# MyRollerShutter_nrf_1-3.net
KiCad netlist of a schematic drawn in EAGLE
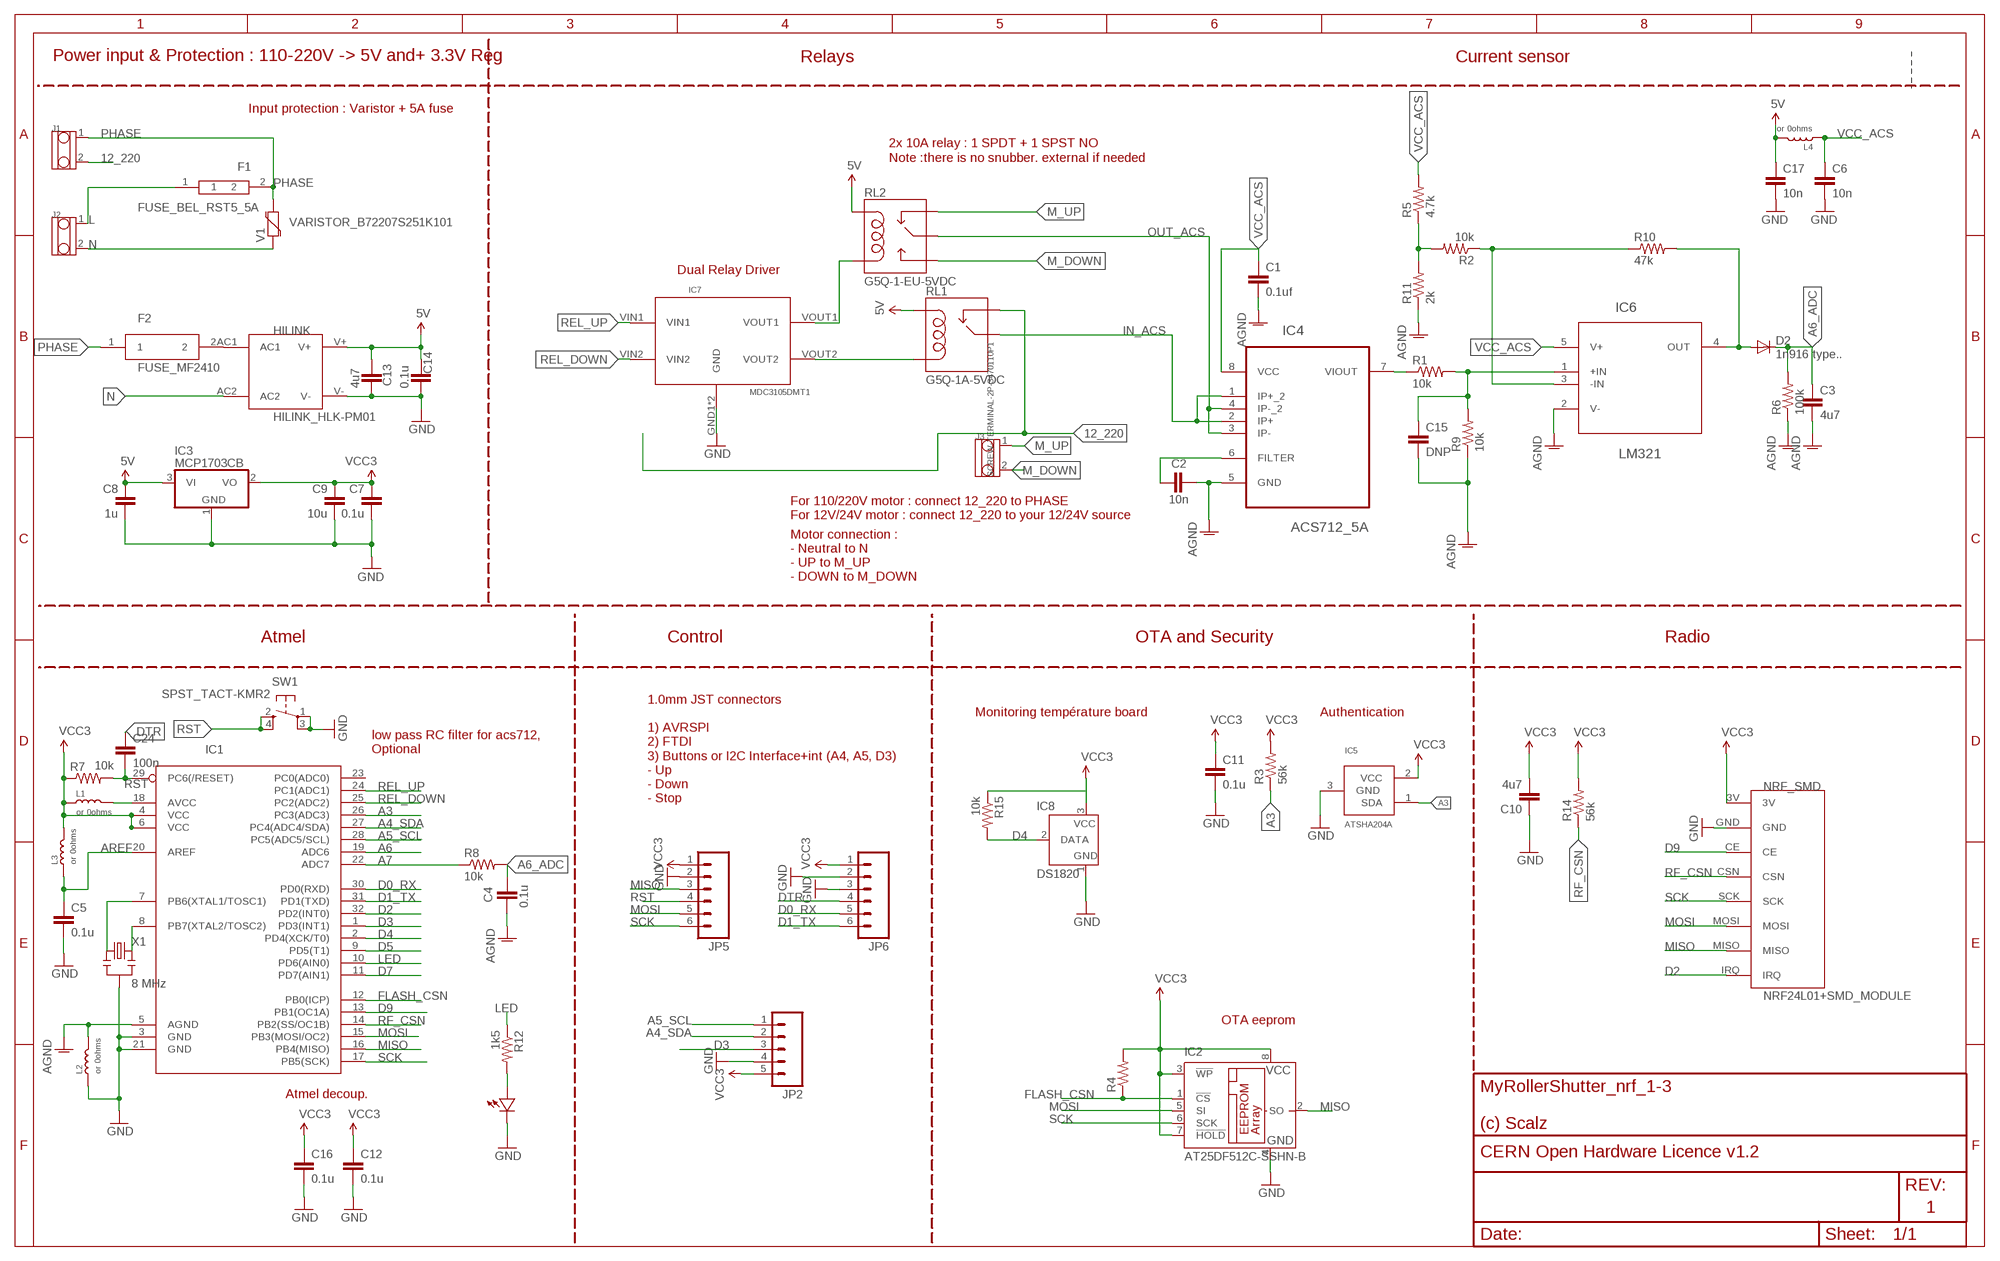
[diagram p0: schematic, sheet 1]

(export (version "E")
  (design (tool "Eeschema 10.0.6"))
  (components
    (comp (ref "C1")
      (value "0.1uf")
      (footprint "eagle-import:0805-CAP")
      (libsource (lib "eagle-import") (part "CAP0805-CAP"))
    )
    (comp (ref "C2")
      (value "10n")
      (footprint "eagle-import:0805-CAP")
      (libsource (lib "eagle-import") (part "CAP0805-CAP"))
    )
    (comp (ref "C3")
      (value "4u7")
      (footprint "eagle-import:0805-CAP")
      (libsource (lib "eagle-import") (part "CAP0805-CAP"))
    )
    (comp (ref "C4")
      (value "0.1u")
      (footprint "eagle-import:0805-CAP")
      (libsource (lib "eagle-import") (part "CAP0805-CAP"))
    )
    (comp (ref "C5")
      (value "0.1u")
      (footprint "eagle-import:0805-CAP")
      (libsource (lib "eagle-import") (part "CAP0805-CAP"))
    )
    (comp (ref "C6")
      (value "10n")
      (footprint "eagle-import:0805-CAP")
      (libsource (lib "eagle-import") (part "CAP0805-CAP"))
    )
    (comp (ref "C7")
      (value "0.1u")
      (footprint "eagle-import:0805-CAP")
      (libsource (lib "eagle-import") (part "CAP0805-CAP"))
    )
    (comp (ref "C8")
      (value "1u")
      (footprint "eagle-import:0805-CAP")
      (libsource (lib "eagle-import") (part "CAP0805-CAP"))
    )
    (comp (ref "C9")
      (value "10u")
      (footprint "eagle-import:0805-CAP")
      (libsource (lib "eagle-import") (part "CAP0805-CAP"))
    )
    (comp (ref "C10")
      (value "4u7")
      (footprint "eagle-import:0805-CAP")
      (libsource (lib "eagle-import") (part "CAP0805-CAP"))
    )
    (comp (ref "C11")
      (value "0.1u")
      (footprint "eagle-import:0805-CAP")
      (libsource (lib "eagle-import") (part "CAP0805-CAP"))
    )
    (comp (ref "C12")
      (value "0.1u")
      (footprint "eagle-import:0805-CAP")
      (libsource (lib "eagle-import") (part "CAP0805-CAP"))
    )
    (comp (ref "C13")
      (value "4u7")
      (footprint "eagle-import:0805-CAP")
      (libsource (lib "eagle-import") (part "CAP0805-CAP"))
    )
    (comp (ref "C14")
      (value "0.1u")
      (footprint "eagle-import:0805-CAP")
      (libsource (lib "eagle-import") (part "CAP0805-CAP"))
    )
    (comp (ref "C15")
      (value "DNP")
      (footprint "eagle-import:0805-CAP")
      (libsource (lib "eagle-import") (part "CAP0805-CAP"))
    )
    (comp (ref "C16")
      (value "0.1u")
      (footprint "eagle-import:0805-CAP")
      (libsource (lib "eagle-import") (part "CAP0805-CAP"))
    )
    (comp (ref "C17")
      (value "10n")
      (footprint "eagle-import:0805-CAP")
      (libsource (lib "eagle-import") (part "CAP0805-CAP"))
    )
    (comp (ref "C24")
      (value "100n")
      (footprint "eagle-import:0805-CAP")
      (libsource (lib "eagle-import") (part "CAP0805-CAP"))
    )
    (comp (ref "D1")
      (value "LED0805")
      (footprint "eagle-import:0805-LED")
      (libsource (lib "eagle-import") (part "LED0805"))
    )
    (comp (ref "D2")
      (value "1n916 type..")
      (footprint "eagle-import:SOD-323")
      (libsource (lib "eagle-import") (part "DIODESOD"))
    )
    (comp (ref "F1")
      (value "FUSE_BEL_RST5_5A")
      (footprint "eagle-import:FUSE_BEL_RST5_5A")
      (libsource (lib "eagle-import") (part "FUSE_BEL_RST5_5A"))
    )
    (comp (ref "F2")
      (value "FUSE_MF2410")
      (footprint "eagle-import:2410")
      (libsource (lib "eagle-import") (part "FUSE_MF2410"))
    )
    (comp (ref "HILINK")
      (value "HILINK_HLK-PM01")
      (footprint "eagle-import:HILINK_HLK-PM01")
      (libsource (lib "eagle-import") (part "HILINK_HLK-PM01"))
    )
    (comp (ref "IC1")
      (value "ATMega-328")
      (footprint "eagle-import:TQFP32-08")
      (libsource (lib "eagle-import") (part "ATMEGA168/328TQFP32"))
    )
    (comp (ref "IC2")
      (value "AT25DF512C-SSHN-B")
      (footprint "eagle-import:SO-08")
      (fields (field (name "MF") "MICROCHIP") (field (name "MPN") "25AA080/SN"))
      (libsource (lib "eagle-import") (part "25SNAA080"))
    )
    (comp (ref "IC3")
      (value "MCP1703CB")
      (footprint "eagle-import:SOT23")
      (libsource (lib "eagle-import") (part "MCP1703CB"))
    )
    (comp (ref "IC4")
      (value "ACS712_5A")
      (footprint "eagle-import:SOIC127P600X175-8N")
      (fields (field (name "MPN") "ACS712ELCTR-20A-T"))
      (libsource (lib "eagle-import") (part "ACS712ELCTR-20A-T"))
    )
    (comp (ref "IC5")
      (value "ATSHA204A")
      (footprint "eagle-import:SOT23")
      (libsource (lib "eagle-import") (part "ATSHA204A"))
    )
    (comp (ref "IC6")
      (value "LM321")
      (footprint "eagle-import:SOT95P285X120-5N")
      (fields (field (name "MPN") "LM321MF"))
      (libsource (lib "eagle-import") (part "LM321MF"))
    )
    (comp (ref "IC7")
      (value "MDC3105DMT1")
      (footprint "eagle-import:MDC3105DMT1")
      (libsource (lib "eagle-import") (part "MDC3105DMT1"))
    )
    (comp (ref "IC8")
      (value "DS1820")
      (footprint "eagle-import:TO92-")
      (libsource (lib "eagle-import") (part "DS1820"))
    )
    (comp (ref "J1")
      (value "SCREW-TERMINAL-2P-3470110P1")
      (footprint "eagle-import:2P-5.0")
      (libsource (lib "eagle-import") (part "SCREW-TERMINAL-2P-3470110P1"))
    )
    (comp (ref "J2")
      (value "SCREW-TERMINAL-2P-3470110P1")
      (footprint "eagle-import:2P-5.0")
      (libsource (lib "eagle-import") (part "SCREW-TERMINAL-2P-3470110P1"))
    )
    (comp (ref "J3")
      (value "SCREW-TERMINAL-2P-3470110P1")
      (footprint "eagle-import:2P-5.0")
      (libsource (lib "eagle-import") (part "SCREW-TERMINAL-2P-3470110P1"))
    )
    (comp (ref "JP2")
      (value "M05SMD")
      (footprint "eagle-import:1X05-1MM")
      (libsource (lib "eagle-import") (part "M05SMD"))
    )
    (comp (ref "JP5")
      (value "M06SMD-1MM")
      (footprint "eagle-import:1X06-1MM")
      (libsource (lib "eagle-import") (part "M06SMD-1MM"))
    )
    (comp (ref "JP6")
      (value "M06SMD-1MM")
      (footprint "eagle-import:1X06-1MM")
      (libsource (lib "eagle-import") (part "M06SMD-1MM"))
    )
    (comp (ref "L1")
      (value "or 0ohms")
      (footprint "eagle-import:L0805")
      (libsource (lib "eagle-import") (part "INDUCTOR/FERRITE-BEAD-0805"))
    )
    (comp (ref "L2")
      (value "or 0ohms")
      (footprint "eagle-import:L0805")
      (libsource (lib "eagle-import") (part "INDUCTOR/FERRITE-BEAD-0805"))
    )
    (comp (ref "L3")
      (value "or 0ohms")
      (footprint "eagle-import:L0805")
      (libsource (lib "eagle-import") (part "INDUCTOR/FERRITE-BEAD-0805"))
    )
    (comp (ref "L4")
      (value "or 0ohms")
      (footprint "eagle-import:L0805")
      (libsource (lib "eagle-import") (part "INDUCTOR/FERRITE-BEAD-0805"))
    )
    (comp (ref "NRF_SMD")
      (value "NRF24L01+SMD_MODULE")
      (footprint "eagle-import:NRF24L01+SMD_MODULE")
      (libsource (lib "eagle-import") (part "NRF24L01+SMD_MODULE"))
    )
    (comp (ref "R1")
      (value "10k")
      (footprint "eagle-import:0805-RES")
      (libsource (lib "eagle-import") (part "RESISTOR0805-RES"))
    )
    (comp (ref "R2")
      (value "10k")
      (footprint "eagle-import:0805-RES")
      (libsource (lib "eagle-import") (part "RESISTOR0805-RES"))
    )
    (comp (ref "R3")
      (value "56k")
      (footprint "eagle-import:0805-RES")
      (libsource (lib "eagle-import") (part "RESISTOR0805-RES"))
    )
    (comp (ref "R4")
      (value "RESISTOR0805-RES")
      (footprint "eagle-import:0805-RES")
      (libsource (lib "eagle-import") (part "RESISTOR0805-RES"))
    )
    (comp (ref "R5")
      (value "4.7k")
      (footprint "eagle-import:0805-RES")
      (libsource (lib "eagle-import") (part "RESISTOR0805-RES"))
    )
    (comp (ref "R6")
      (value "100k")
      (footprint "eagle-import:0805-RES")
      (libsource (lib "eagle-import") (part "RESISTOR0805-RES"))
    )
    (comp (ref "R7")
      (value "10k")
      (footprint "eagle-import:0805-RES")
      (libsource (lib "eagle-import") (part "RESISTOR0805-RES"))
    )
    (comp (ref "R8")
      (value "10k")
      (footprint "eagle-import:0805-RES")
      (libsource (lib "eagle-import") (part "RESISTOR0805-RES"))
    )
    (comp (ref "R9")
      (value "10k")
      (footprint "eagle-import:0805-RES")
      (libsource (lib "eagle-import") (part "RESISTOR0805-RES"))
    )
    (comp (ref "R10")
      (value "47k")
      (footprint "eagle-import:0805-RES")
      (libsource (lib "eagle-import") (part "RESISTOR0805-RES"))
    )
    (comp (ref "R11")
      (value "2k")
      (footprint "eagle-import:0805-RES")
      (libsource (lib "eagle-import") (part "RESISTOR0805-RES"))
    )
    (comp (ref "R12")
      (value "1k5")
      (footprint "eagle-import:0805-RES")
      (libsource (lib "eagle-import") (part "RESISTOR0805-RES"))
    )
    (comp (ref "R14")
      (value "56k")
      (footprint "eagle-import:0805-RES")
      (libsource (lib "eagle-import") (part "RESISTOR0805-RES"))
    )
    (comp (ref "R15")
      (value "10k")
      (footprint "eagle-import:0805-RES")
      (libsource (lib "eagle-import") (part "RESISTOR0805-RES"))
    )
    (comp (ref "RL1")
      (value "G5Q-1A-5VDC")
      (footprint "eagle-import:G5Q_SINGLE")
      (libsource (lib "eagle-import") (part "G5Q_SINGLE"))
    )
    (comp (ref "RL2")
      (value "G5Q-1-EU-5VDC")
      (footprint "eagle-import:RELAY-G5Q")
      (libsource (lib "eagle-import") (part "RELAYPTH"))
    )
    (comp (ref "SW1")
      (value "SPST_TACT-KMR2")
      (footprint "eagle-import:KMR2")
      (libsource (lib "eagle-import") (part "SPST_TACT-KMR2"))
    )
    (comp (ref "V1")
      (value "VARISTOR_B72207S251K101")
      (footprint "eagle-import:VARISTOR_B72207S251K101")
      (libsource (lib "eagle-import") (part "VARISTOR_B72207S251K101"))
    )
    (comp (ref "X1")
      (value "8 MHz")
      (footprint "eagle-import:RESONATOR-SMD")
      (libsource (lib "eagle-import") (part "RESONATORSMD"))
    )
  )
  (nets
    (net (code "1") (name "/A4_SDA") (class "Default")
      (node (ref "IC1") (pin "27") (pinfunction "PC4(ADC4/SDA)_27") (pintype "bidirectional"))
      (node (ref "JP2") (pin "2") (pinfunction "2_2") (pintype "passive"))
    )
    (net (code "2") (name "/A5_SCL") (class "Default")
      (node (ref "IC1") (pin "28") (pinfunction "PC5(ADC5/SCL)_28") (pintype "bidirectional"))
      (node (ref "JP2") (pin "1") (pinfunction "1_1") (pintype "passive"))
    )
    (net (code "3") (name "/A6") (class "Default")
      (node (ref "IC1") (pin "19") (pinfunction "ADC6_19") (pintype "bidirectional"))
    )
    (net (code "4") (name "/A7") (class "Default")
      (node (ref "IC1") (pin "22") (pinfunction "ADC7_22") (pintype "bidirectional"))
      (node (ref "R8") (pin "1") (pinfunction "1_1") (pintype "passive"))
    )
    (net (code "5") (name "/AREF") (class "Default")
      (node (ref "C5") (pin "1") (pinfunction "1_1") (pintype "passive"))
      (node (ref "IC1") (pin "20") (pinfunction "AREF_20") (pintype "bidirectional"))
      (node (ref "L3") (pin "1") (pinfunction "1_1") (pintype "passive"))
    )
    (net (code "6") (name "/D0_RX") (class "Default")
      (node (ref "IC1") (pin "30") (pinfunction "PD0(RXD)_30") (pintype "bidirectional"))
      (node (ref "JP6") (pin "5") (pinfunction "5_5") (pintype "passive"))
    )
    (net (code "7") (name "/D1_TX") (class "Default")
      (node (ref "IC1") (pin "31") (pinfunction "PD1(TXD)_31") (pintype "bidirectional"))
      (node (ref "JP6") (pin "6") (pinfunction "6_6") (pintype "passive"))
    )
    (net (code "8") (name "/D2") (class "Default")
      (node (ref "IC1") (pin "32") (pinfunction "PD2(INT0)_32") (pintype "bidirectional"))
      (node (ref "NRF_SMD") (pin "IRQ") (pinfunction "IRQ_IRQ") (pintype "bidirectional"))
    )
    (net (code "9") (name "/D3") (class "Default")
      (node (ref "IC1") (pin "1") (pinfunction "PD3(INT1)_1") (pintype "bidirectional"))
      (node (ref "JP2") (pin "3") (pinfunction "3_3") (pintype "passive"))
    )
    (net (code "10") (name "/D4") (class "Default")
      (node (ref "IC1") (pin "2") (pinfunction "PD4(XCK/T0)_2") (pintype "bidirectional"))
      (node (ref "IC8") (pin "2") (pinfunction "DATA_2") (pintype "input"))
      (node (ref "R15") (pin "2") (pinfunction "2_2") (pintype "passive"))
    )
    (net (code "11") (name "/D5") (class "Default")
      (node (ref "IC1") (pin "9") (pinfunction "PD5(T1)_9") (pintype "bidirectional"))
    )
    (net (code "12") (name "/D7") (class "Default")
      (node (ref "IC1") (pin "11") (pinfunction "PD7(AIN1)_11") (pintype "bidirectional"))
    )
    (net (code "13") (name "/D9") (class "Default")
      (node (ref "IC1") (pin "13") (pinfunction "PB1(OC1A)_13") (pintype "bidirectional"))
      (node (ref "NRF_SMD") (pin "CE") (pinfunction "CE_CE") (pintype "bidirectional"))
    )
    (net (code "14") (name "/FLASH_CSN") (class "Default")
      (node (ref "IC1") (pin "12") (pinfunction "PB0(ICP)_12") (pintype "bidirectional"))
      (node (ref "IC2") (pin "1") (pinfunction "~{CS}_1") (pintype "input"))
      (node (ref "R4") (pin "1") (pinfunction "1_1") (pintype "passive"))
    )
    (net (code "15") (name "/IN_ACS") (class "Default")
      (node (ref "IC4") (pin "1") (pinfunction "IP+_2_1") (pintype "input"))
      (node (ref "IC4") (pin "2") (pinfunction "IP+_2") (pintype "input"))
      (node (ref "RL1") (pin "2") (pinfunction "MAIN_2") (pintype "bidirectional"))
    )
    (net (code "16") (name "/L") (class "Default")
      (node (ref "F1") (pin "1") (pinfunction "1_1") (pintype "bidirectional"))
      (node (ref "J2") (pin "1") (pinfunction "1_1") (pintype "bidirectional"))
    )
    (net (code "17") (name "/LED") (class "Default")
      (node (ref "IC1") (pin "10") (pinfunction "PD6(AIN0)_10") (pintype "bidirectional"))
      (node (ref "R12") (pin "1") (pinfunction "1_1") (pintype "passive"))
    )
    (net (code "18") (name "/MISO") (class "Default")
      (node (ref "IC1") (pin "16") (pinfunction "PB4(MISO)_16") (pintype "bidirectional"))
      (node (ref "IC2") (pin "2") (pinfunction "SO_2") (pintype "bidirectional"))
      (node (ref "JP5") (pin "3") (pinfunction "3_3") (pintype "passive"))
      (node (ref "NRF_SMD") (pin "MISO") (pinfunction "MISO_MISO") (pintype "bidirectional"))
    )
    (net (code "19") (name "/MOSI") (class "Default")
      (node (ref "IC1") (pin "15") (pinfunction "PB3(MOSI/OC2)_15") (pintype "bidirectional"))
      (node (ref "IC2") (pin "5") (pinfunction "SI_5") (pintype "input"))
      (node (ref "JP5") (pin "5") (pinfunction "5_5") (pintype "passive"))
      (node (ref "NRF_SMD") (pin "MOSI") (pinfunction "MOSI_MOSI") (pintype "bidirectional"))
    )
    (net (code "20") (name "/OUT_ACS") (class "Default")
      (node (ref "IC4") (pin "3") (pinfunction "IP-_3") (pintype "input"))
      (node (ref "IC4") (pin "4") (pinfunction "IP-_2_4") (pintype "input"))
      (node (ref "RL2") (pin "2") (pinfunction "MAIN_2") (pintype "bidirectional"))
    )
    (net (code "21") (name "/SCK") (class "Default")
      (node (ref "IC1") (pin "17") (pinfunction "PB5(SCK)_17") (pintype "bidirectional"))
      (node (ref "IC2") (pin "6") (pinfunction "SCK_6") (pintype "input"))
      (node (ref "JP5") (pin "6") (pinfunction "6_6") (pintype "passive"))
      (node (ref "NRF_SMD") (pin "SCK") (pinfunction "SCK_SCK") (pintype "bidirectional"))
    )
    (net (code "22") (name "5V") (class "Default")
      (node (ref "C13") (pin "1") (pinfunction "1_1") (pintype "passive"))
      (node (ref "C14") (pin "1") (pinfunction "1_1") (pintype "passive"))
      (node (ref "C17") (pin "1") (pinfunction "1_1") (pintype "passive"))
      (node (ref "C8") (pin "1") (pinfunction "1_1") (pintype "passive"))
      (node (ref "HILINK") (pin "V+") (pinfunction "V+_V+") (pintype "bidirectional"))
      (node (ref "IC3") (pin "3") (pinfunction "VI_3") (pintype "input"))
      (node (ref "L4") (pin "2") (pinfunction "2_2") (pintype "passive"))
      (node (ref "RL1") (pin "1") (pinfunction "COIL1_1") (pintype "bidirectional"))
      (node (ref "RL2") (pin "5") (pinfunction "COIL1_5") (pintype "bidirectional"))
    )
    (net (code "23") (name "12_220") (class "Default")
      (node (ref "J1") (pin "2") (pinfunction "2_2") (pintype "bidirectional"))
      (node (ref "RL1") (pin "3") (pinfunction "NC_3") (pintype "bidirectional"))
    )
    (net (code "24") (name "A3") (class "Default")
      (node (ref "IC1") (pin "26") (pinfunction "PC3(ADC3)_26") (pintype "bidirectional"))
      (node (ref "IC5") (pin "1") (pinfunction "SDA_1") (pintype "bidirectional"))
      (node (ref "R3") (pin "1") (pinfunction "1_1") (pintype "passive"))
    )
    (net (code "25") (name "A6_ADC") (class "Default")
      (node (ref "C3") (pin "1") (pinfunction "1_1") (pintype "passive"))
      (node (ref "C4") (pin "2") (pinfunction "2_2") (pintype "passive"))
      (node (ref "D2") (pin "1") (pinfunction "C_1") (pintype "passive"))
      (node (ref "R6") (pin "2") (pinfunction "2_2") (pintype "passive"))
      (node (ref "R8") (pin "2") (pinfunction "2_2") (pintype "passive"))
    )
    (net (code "26") (name "AGND") (class "Default")
      (node (ref "C1") (pin "2") (pinfunction "2_2") (pintype "passive"))
      (node (ref "C15") (pin "2") (pinfunction "2_2") (pintype "passive"))
      (node (ref "C2") (pin "2") (pinfunction "2_2") (pintype "passive"))
      (node (ref "C3") (pin "2") (pinfunction "2_2") (pintype "passive"))
      (node (ref "C4") (pin "1") (pinfunction "1_1") (pintype "passive"))
      (node (ref "IC1") (pin "5") (pinfunction "AGND_5") (pintype "bidirectional"))
      (node (ref "IC4") (pin "5") (pinfunction "GND_5") (pintype "passive"))
      (node (ref "IC6") (pin "2") (pinfunction "V-_2") (pintype "power_in"))
      (node (ref "L2") (pin "2") (pinfunction "2_2") (pintype "passive"))
      (node (ref "R11") (pin "1") (pinfunction "1_1") (pintype "passive"))
      (node (ref "R6") (pin "1") (pinfunction "1_1") (pintype "passive"))
      (node (ref "R9") (pin "1") (pinfunction "1_1") (pintype "passive"))
    )
    (net (code "27") (name "DTR") (class "Default")
      (node (ref "C24") (pin "1") (pinfunction "1_1") (pintype "passive"))
      (node (ref "JP6") (pin "4") (pinfunction "4_4") (pintype "passive"))
    )
    (net (code "28") (name "GND") (class "Default")
      (node (ref "C10") (pin "1") (pinfunction "1_1") (pintype "passive"))
      (node (ref "C11") (pin "2") (pinfunction "2_2") (pintype "passive"))
      (node (ref "C12") (pin "2") (pinfunction "2_2") (pintype "passive"))
      (node (ref "C13") (pin "2") (pinfunction "2_2") (pintype "passive"))
      (node (ref "C14") (pin "2") (pinfunction "2_2") (pintype "passive"))
      (node (ref "C16") (pin "2") (pinfunction "2_2") (pintype "passive"))
      (node (ref "C17") (pin "2") (pinfunction "2_2") (pintype "passive"))
      (node (ref "C5") (pin "2") (pinfunction "2_2") (pintype "passive"))
      (node (ref "C6") (pin "2") (pinfunction "2_2") (pintype "passive"))
      (node (ref "C7") (pin "2") (pinfunction "2_2") (pintype "passive"))
      (node (ref "C8") (pin "2") (pinfunction "2_2") (pintype "passive"))
      (node (ref "C9") (pin "2") (pinfunction "2_2") (pintype "passive"))
      (node (ref "D1") (pin "MINUS") (pinfunction "MINUS_MINUS") (pintype "passive"))
      (node (ref "HILINK") (pin "V-") (pinfunction "V-_V-") (pintype "bidirectional"))
      (node (ref "IC1") (pin "21") (pinfunction "GND_21") (pintype "bidirectional"))
      (node (ref "IC1") (pin "3") (pinfunction "GND_3") (pintype "bidirectional"))
      (node (ref "IC2") (pin "4") (pinfunction "GND_4") (pintype "power_in"))
      (node (ref "IC3") (pin "1") (pinfunction "GND_1") (pintype "passive"))
      (node (ref "IC5") (pin "3") (pinfunction "GND_3") (pintype "bidirectional"))
      (node (ref "IC7") (pin "GND1") (pinfunction "GND_GND1") (pintype "bidirectional"))
      (node (ref "IC7") (pin "GND2") (pinfunction "GND_GND2") (pintype "bidirectional"))
      (node (ref "IC8") (pin "1") (pinfunction "GND_1") (pintype "passive"))
      (node (ref "JP2") (pin "4") (pinfunction "4_4") (pintype "passive"))
      (node (ref "JP5") (pin "2") (pinfunction "2_2") (pintype "passive"))
      (node (ref "JP6") (pin "2") (pinfunction "2_2") (pintype "passive"))
      (node (ref "JP6") (pin "3") (pinfunction "3_3") (pintype "passive"))
      (node (ref "L2") (pin "1") (pinfunction "1_1") (pintype "passive"))
      (node (ref "NRF_SMD") (pin "GND") (pinfunction "GND_GND") (pintype "bidirectional"))
      (node (ref "SW1") (pin "1") (pinfunction "P_1") (pintype "passive"))
      (node (ref "SW1") (pin "3") (pinfunction "P1_3") (pintype "passive"))
      (node (ref "X1") (pin "2") (pinfunction "2_2") (pintype "passive"))
    )
    (net (code "29") (name "M_DOWN") (class "Default")
      (node (ref "J3") (pin "2") (pinfunction "2_2") (pintype "bidirectional"))
      (node (ref "RL2") (pin "3") (pinfunction "NO_3") (pintype "bidirectional"))
    )
    (net (code "30") (name "M_UP") (class "Default")
      (node (ref "J3") (pin "1") (pinfunction "1_1") (pintype "bidirectional"))
      (node (ref "RL2") (pin "4") (pinfunction "NC_4") (pintype "bidirectional"))
    )
    (net (code "31") (name "N") (class "Default")
      (node (ref "HILINK") (pin "AC2") (pinfunction "AC2_AC2") (pintype "bidirectional"))
      (node (ref "J2") (pin "2") (pinfunction "2_2") (pintype "bidirectional"))
      (node (ref "V1") (pin "1") (pinfunction "1_1") (pintype "passive"))
    )
    (net (code "32") (name "Net-(D1-PadPLUS)") (class "Default")
      (node (ref "D1") (pin "PLUS") (pinfunction "PLUS_PLUS") (pintype "passive"))
      (node (ref "R12") (pin "2") (pinfunction "2_2") (pintype "passive"))
    )
    (net (code "33") (name "Net-(D2-A)") (class "Default")
      (node (ref "D2") (pin "2") (pinfunction "A_2") (pintype "passive"))
      (node (ref "IC6") (pin "4") (pinfunction "OUT_4") (pintype "output"))
      (node (ref "R10") (pin "2") (pinfunction "2_2") (pintype "passive"))
    )
    (net (code "34") (name "Net-(F2-Pad2)") (class "Default")
      (node (ref "F2") (pin "2") (pinfunction "2_2") (pintype "bidirectional"))
      (node (ref "HILINK") (pin "AC1") (pinfunction "AC1_AC1") (pintype "bidirectional"))
    )
    (net (code "35") (name "Net-(IC1-AVCC)") (class "Default")
      (node (ref "IC1") (pin "18") (pinfunction "AVCC_18") (pintype "bidirectional"))
      (node (ref "L1") (pin "2") (pinfunction "2_2") (pintype "passive"))
    )
    (net (code "36") (name "Net-(IC1-PB6(XTAL1{slash}TOSC1))") (class "Default")
      (node (ref "IC1") (pin "7") (pinfunction "PB6(XTAL1/TOSC1)_7") (pintype "bidirectional"))
      (node (ref "X1") (pin "1") (pinfunction "1_1") (pintype "passive"))
    )
    (net (code "37") (name "Net-(IC1-PB7(XTAL2{slash}TOSC2))") (class "Default")
      (node (ref "IC1") (pin "8") (pinfunction "PB7(XTAL2/TOSC2)_8") (pintype "bidirectional"))
      (node (ref "X1") (pin "3") (pinfunction "3_3") (pintype "passive"))
    )
    (net (code "38") (name "Net-(IC4-FILTER)") (class "Default")
      (node (ref "C2") (pin "1") (pinfunction "1_1") (pintype "passive"))
      (node (ref "IC4") (pin "6") (pinfunction "FILTER_6") (pintype "input"))
    )
    (net (code "39") (name "Net-(IC4-VIOUT)") (class "Default")
      (node (ref "IC4") (pin "7") (pinfunction "VIOUT_7") (pintype "output"))
      (node (ref "R1") (pin "1") (pinfunction "1_1") (pintype "passive"))
    )
    (net (code "40") (name "Net-(IC6-+IN)") (class "Default")
      (node (ref "C15") (pin "1") (pinfunction "1_1") (pintype "passive"))
      (node (ref "IC6") (pin "1") (pinfunction "+IN_1") (pintype "input"))
      (node (ref "R1") (pin "2") (pinfunction "2_2") (pintype "passive"))
      (node (ref "R9") (pin "2") (pinfunction "2_2") (pintype "passive"))
    )
    (net (code "41") (name "Net-(IC6--IN)") (class "Default")
      (node (ref "IC6") (pin "3") (pinfunction "-IN_3") (pintype "input"))
      (node (ref "R10") (pin "1") (pinfunction "1_1") (pintype "passive"))
      (node (ref "R2") (pin "1") (pinfunction "1_1") (pintype "passive"))
    )
    (net (code "42") (name "Net-(R11-Pad2)") (class "Default")
      (node (ref "R11") (pin "2") (pinfunction "2_2") (pintype "passive"))
      (node (ref "R2") (pin "2") (pinfunction "2_2") (pintype "passive"))
      (node (ref "R5") (pin "1") (pinfunction "1_1") (pintype "passive"))
    )
    (net (code "43") (name "Net-(RL1-COIL2)") (class "Default")
      (node (ref "IC7") (pin "VOUT2") (pinfunction "VOUT2_VOUT2") (pintype "bidirectional"))
      (node (ref "RL1") (pin "5") (pinfunction "COIL2_5") (pintype "bidirectional"))
    )
    (net (code "44") (name "Net-(RL2-COIL2)") (class "Default")
      (node (ref "IC7") (pin "VOUT1") (pinfunction "VOUT1_VOUT1") (pintype "bidirectional"))
      (node (ref "RL2") (pin "1") (pinfunction "COIL2_1") (pintype "bidirectional"))
    )
    (net (code "45") (name "PHASE") (class "Default")
      (node (ref "F1") (pin "2") (pinfunction "2_2") (pintype "bidirectional"))
      (node (ref "F2") (pin "1") (pinfunction "1_1") (pintype "bidirectional"))
      (node (ref "J1") (pin "1") (pinfunction "1_1") (pintype "bidirectional"))
      (node (ref "V1") (pin "2") (pinfunction "2_2") (pintype "passive"))
    )
    (net (code "46") (name "REL_DOWN") (class "Default")
      (node (ref "IC1") (pin "25") (pinfunction "PC2(ADC2)_25") (pintype "bidirectional"))
      (node (ref "IC7") (pin "VIN2") (pinfunction "VIN2_VIN2") (pintype "bidirectional"))
    )
    (net (code "47") (name "REL_UP") (class "Default")
      (node (ref "IC1") (pin "24") (pinfunction "PC1(ADC1)_24") (pintype "bidirectional"))
      (node (ref "IC7") (pin "VIN1") (pinfunction "VIN1_VIN1") (pintype "bidirectional"))
    )
    (net (code "48") (name "RF_CSN") (class "Default")
      (node (ref "IC1") (pin "14") (pinfunction "PB2(SS/OC1B)_14") (pintype "bidirectional"))
      (node (ref "R14") (pin "1") (pinfunction "1_1") (pintype "passive"))
    )
    (net (code "49") (name "RST") (class "Default")
      (node (ref "C24") (pin "2") (pinfunction "2_2") (pintype "passive"))
      (node (ref "IC1") (pin "29") (pinfunction "PC6(/RESET)_29") (pintype "bidirectional"))
      (node (ref "JP5") (pin "4") (pinfunction "4_4") (pintype "passive"))
      (node (ref "R7") (pin "2") (pinfunction "2_2") (pintype "passive"))
      (node (ref "SW1") (pin "2") (pinfunction "S_2") (pintype "passive"))
      (node (ref "SW1") (pin "4") (pinfunction "S1_4") (pintype "passive"))
    )
    (net (code "50") (name "VCC3") (class "Default")
      (node (ref "C10") (pin "2") (pinfunction "2_2") (pintype "passive"))
      (node (ref "C11") (pin "1") (pinfunction "1_1") (pintype "passive"))
      (node (ref "C12") (pin "1") (pinfunction "1_1") (pintype "passive"))
      (node (ref "C16") (pin "1") (pinfunction "1_1") (pintype "passive"))
      (node (ref "C7") (pin "1") (pinfunction "1_1") (pintype "passive"))
      (node (ref "C9") (pin "1") (pinfunction "1_1") (pintype "passive"))
      (node (ref "IC1") (pin "4") (pinfunction "VCC_4") (pintype "bidirectional"))
      (node (ref "IC1") (pin "6") (pinfunction "VCC_6") (pintype "bidirectional"))
      (node (ref "IC2") (pin "3") (pinfunction "~{WP}_3") (pintype "input"))
      (node (ref "IC2") (pin "7") (pinfunction "~{HOLD}_7") (pintype "input"))
      (node (ref "IC2") (pin "8") (pinfunction "VCC_8") (pintype "power_in"))
      (node (ref "IC3") (pin "2") (pinfunction "VO_2") (pintype "passive"))
      (node (ref "IC5") (pin "2") (pinfunction "VCC_2") (pintype "bidirectional"))
      (node (ref "IC8") (pin "3") (pinfunction "VCC_3") (pintype "passive"))
      (node (ref "JP2") (pin "5") (pinfunction "5_5") (pintype "passive"))
      (node (ref "JP5") (pin "1") (pinfunction "1_1") (pintype "passive"))
      (node (ref "JP6") (pin "1") (pinfunction "1_1") (pintype "passive"))
      (node (ref "L1") (pin "1") (pinfunction "1_1") (pintype "passive"))
      (node (ref "L3") (pin "2") (pinfunction "2_2") (pintype "passive"))
      (node (ref "NRF_SMD") (pin "3V") (pinfunction "3V_3V") (pintype "bidirectional"))
      (node (ref "R14") (pin "2") (pinfunction "2_2") (pintype "passive"))
      (node (ref "R15") (pin "1") (pinfunction "1_1") (pintype "passive"))
      (node (ref "R3") (pin "2") (pinfunction "2_2") (pintype "passive"))
      (node (ref "R4") (pin "2") (pinfunction "2_2") (pintype "passive"))
      (node (ref "R7") (pin "1") (pinfunction "1_1") (pintype "passive"))
    )
    (net (code "51") (name "VCC_ACS") (class "Default")
      (node (ref "C1") (pin "1") (pinfunction "1_1") (pintype "passive"))
      (node (ref "C6") (pin "1") (pinfunction "1_1") (pintype "passive"))
      (node (ref "IC4") (pin "8") (pinfunction "VCC_8") (pintype "power_in"))
      (node (ref "IC6") (pin "5") (pinfunction "V+_5") (pintype "power_in"))
      (node (ref "L4") (pin "1") (pinfunction "1_1") (pintype "passive"))
      (node (ref "R5") (pin "2") (pinfunction "2_2") (pintype "passive"))
    )
    (net (code "52") (name "unconnected-(IC1-PC0(ADC0)-Pad23)") (class "Default")
      (node (ref "IC1") (pin "23") (pinfunction "PC0(ADC0)_23") (pintype "bidirectional"))
    )
    (net (code "53") (name "unconnected-(NRF_SMD-PadCSN)") (class "Default")
      (node (ref "NRF_SMD") (pin "CSN") (pinfunction "CSN_CSN") (pintype "bidirectional"))
    )
  )
)
